# Power.net
KiCad netlist of a schematic drawn in Altium Designer
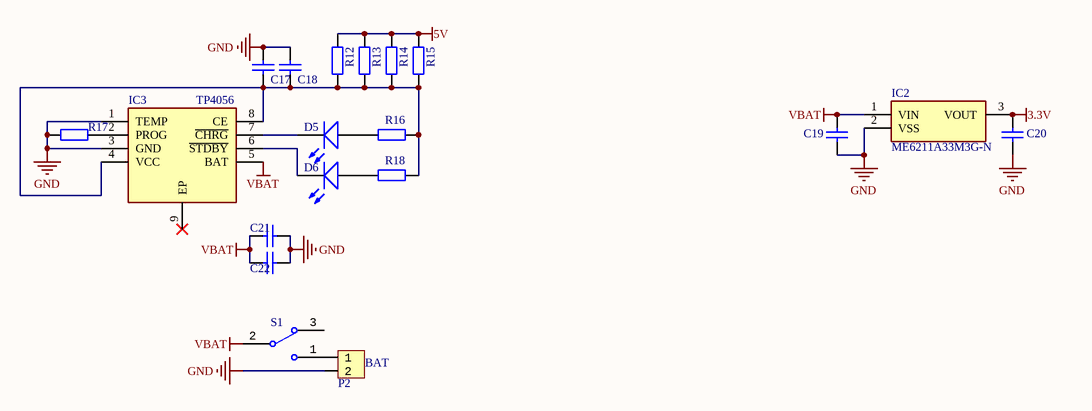
[diagram p0: Power.SchDoc]

(export (version "E")
  (design (tool "Eeschema 10.0.6"))
  (components
    (comp (ref "C17")
      (value "10nF")
      (footprint "CAP-0603")
      (description "贴片电容")
      (libsource (lib "Power_Lib_Altium") (part "CAP"))
    )
    (comp (ref "C18")
      (value "100nF")
      (footprint "CAP-0603")
      (description "贴片电容")
      (libsource (lib "Power_Lib_Altium") (part "CAP"))
    )
    (comp (ref "C19")
      (value "1uF")
      (footprint "CAP-0603")
      (description "贴片电容")
      (libsource (lib "Power_Lib_Altium") (part "CAP"))
    )
    (comp (ref "C20")
      (value "1uF")
      (footprint "CAP-0603")
      (description "贴片电容")
      (libsource (lib "Power_Lib_Altium") (part "CAP"))
    )
    (comp (ref "C21")
      (value "100nF")
      (footprint "CAP-0603")
      (description "贴片电容")
      (libsource (lib "Power_Lib_Altium") (part "CAP"))
    )
    (comp (ref "C22")
      (value "10nF")
      (footprint "CAP-0603")
      (description "贴片电容")
      (libsource (lib "Power_Lib_Altium") (part "CAP"))
    )
    (comp (ref "D5")
      (value "RED")
      (footprint "LED-0603")
      (description "发光二极管")
      (libsource (lib "Power_Lib_Altium") (part "LED"))
    )
    (comp (ref "D6")
      (value "RED")
      (footprint "LED-0603")
      (description "发光二极管")
      (libsource (lib "Power_Lib_Altium") (part "LED"))
    )
    (comp (ref "IC2")
      (value "ME6211A33M3G-N")
      (footprint "SOT-23-3")
      (description "线性稳压")
      (fields (field (name "MANUFACTURER_PART_NUMBER") "SI2302DS") (field (name "RS PART NUMBER") "7983053P"))
      (libsource (lib "Power_Lib_Altium") (part "ME6211A33M3G-N"))
    )
    (comp (ref "IC3")
      (value "TP4056")
      (footprint "MSOP_E120_P0.5_10")
      (description "锂电池充电（1A 线性）")
      (fields (field (name "MANUFACTURER_PART_NUMBER") "TP4056-42-ESOP8"))
      (libsource (lib "Power_Lib_Altium") (part "TP4056"))
    )
    (comp (ref "P2")
      (value "HDR1x2_2.54")
      (footprint "HDR1X2_2.54_90")
      (description "Header")
      (libsource (lib "Power_Lib_Altium") (part "HDR1x2_2.54"))
    )
    (comp (ref "R12")
      (value "1R")
      (footprint "R-0603")
      (description "贴片电阻")
      (libsource (lib "Power_Lib_Altium") (part "RES"))
    )
    (comp (ref "R13")
      (value "1R")
      (footprint "R-0603")
      (description "贴片电阻")
      (libsource (lib "Power_Lib_Altium") (part "RES"))
    )
    (comp (ref "R14")
      (value "1R")
      (footprint "R-0603")
      (description "贴片电阻")
      (libsource (lib "Power_Lib_Altium") (part "RES"))
    )
    (comp (ref "R15")
      (value "1R")
      (footprint "R-0603")
      (description "贴片电阻")
      (libsource (lib "Power_Lib_Altium") (part "RES"))
    )
    (comp (ref "R16")
      (value "2K")
      (footprint "R-0603")
      (description "贴片电阻")
      (libsource (lib "") (part "RES_1"))
    )
    (comp (ref "R17")
      (value "1.2K")
      (footprint "R-0603")
      (description "贴片电阻")
      (libsource (lib "") (part "RES_1"))
    )
    (comp (ref "R18")
      (value "10K")
      (footprint "R-0603")
      (description "贴片电阻")
      (libsource (lib "") (part "RES_1"))
    )
    (comp (ref "S1")
      (value "Switch_SPDT")
      (footprint "SwitchSPDT_2.8X6.6_90")
      (libsource (lib "Power_Lib_Altium") (part "Switch_SPDT"))
    )
  )
  (nets
    (net (code "1") (name "3.3V") (class "Default")
      (node (ref "C20") (pin "2") (pinfunction "2_2") (pintype "passive"))
      (node (ref "IC2") (pin "3") (pinfunction "VOUT_3") (pintype "passive"))
    )
    (net (code "2") (name "5V") (class "Default")
      (node (ref "R12") (pin "2") (pinfunction "2_2") (pintype "passive"))
      (node (ref "R13") (pin "2") (pinfunction "2_2") (pintype "passive"))
      (node (ref "R14") (pin "2") (pinfunction "2_2") (pintype "passive"))
      (node (ref "R15") (pin "2") (pinfunction "2_2") (pintype "passive"))
    )
    (net (code "3") (name "GND") (class "Default")
      (node (ref "C17") (pin "2") (pinfunction "2_2") (pintype "passive"))
      (node (ref "C18") (pin "2") (pinfunction "2_2") (pintype "passive"))
      (node (ref "C19") (pin "1") (pinfunction "1_1") (pintype "passive"))
      (node (ref "C20") (pin "1") (pinfunction "1_1") (pintype "passive"))
      (node (ref "C21") (pin "1") (pinfunction "1_1") (pintype "passive"))
      (node (ref "C22") (pin "1") (pinfunction "1_1") (pintype "passive"))
      (node (ref "IC2") (pin "2") (pinfunction "VSS_2") (pintype "passive"))
      (node (ref "IC3") (pin "1") (pinfunction "TEMP_1") (pintype "passive"))
      (node (ref "IC3") (pin "3") (pinfunction "GND_3") (pintype "passive"))
      (node (ref "P2") (pin "2") (pinfunction "2_2") (pintype "passive"))
      (node (ref "R17") (pin "1") (pinfunction "1_1") (pintype "passive"))
    )
    (net (code "4") (name "Net-(D5-PadA)") (class "Default")
      (node (ref "D5") (pin "A") (pinfunction "A_A") (pintype "passive"))
      (node (ref "R16") (pin "1") (pinfunction "1_1") (pintype "passive"))
    )
    (net (code "5") (name "Net-(D6-PadA)") (class "Default")
      (node (ref "D6") (pin "A") (pinfunction "A_A") (pintype "passive"))
      (node (ref "R18") (pin "1") (pinfunction "1_1") (pintype "passive"))
    )
    (net (code "6") (name "Net-(IC3-CE)") (class "Default")
      (node (ref "C17") (pin "1") (pinfunction "1_1") (pintype "passive"))
      (node (ref "C18") (pin "1") (pinfunction "1_1") (pintype "passive"))
      (node (ref "IC3") (pin "4") (pinfunction "VCC_4") (pintype "passive"))
      (node (ref "IC3") (pin "8") (pinfunction "CE_8") (pintype "passive"))
      (node (ref "R12") (pin "1") (pinfunction "1_1") (pintype "passive"))
      (node (ref "R13") (pin "1") (pinfunction "1_1") (pintype "passive"))
      (node (ref "R14") (pin "1") (pinfunction "1_1") (pintype "passive"))
      (node (ref "R15") (pin "1") (pinfunction "1_1") (pintype "passive"))
      (node (ref "R16") (pin "2") (pinfunction "2_2") (pintype "passive"))
      (node (ref "R18") (pin "2") (pinfunction "2_2") (pintype "passive"))
    )
    (net (code "7") (name "Net-(IC3-PROG)") (class "Default")
      (node (ref "IC3") (pin "2") (pinfunction "PROG_2") (pintype "passive"))
      (node (ref "R17") (pin "2") (pinfunction "2_2") (pintype "passive"))
    )
    (net (code "8") (name "Net-(IC3-~{CHRG})") (class "Default")
      (node (ref "D5") (pin "K") (pinfunction "K_K") (pintype "passive"))
      (node (ref "IC3") (pin "7") (pinfunction "~{CHRG}_7") (pintype "passive"))
    )
    (net (code "9") (name "Net-(IC3-~{STDBY})") (class "Default")
      (node (ref "D6") (pin "K") (pinfunction "K_K") (pintype "passive"))
      (node (ref "IC3") (pin "6") (pinfunction "~{STDBY}_6") (pintype "passive"))
    )
    (net (code "10") (name "Net-(P2-Pad1)") (class "Default")
      (node (ref "P2") (pin "1") (pinfunction "1_1") (pintype "passive"))
      (node (ref "S1") (pin "1") (pinfunction "1_1") (pintype "passive"))
    )
    (net (code "11") (name "VBAT") (class "Default")
      (node (ref "C19") (pin "2") (pinfunction "2_2") (pintype "passive"))
      (node (ref "C21") (pin "2") (pinfunction "2_2") (pintype "passive"))
      (node (ref "C22") (pin "2") (pinfunction "2_2") (pintype "passive"))
      (node (ref "IC2") (pin "1") (pinfunction "VIN_1") (pintype "passive"))
      (node (ref "IC3") (pin "5") (pinfunction "BAT_5") (pintype "passive"))
      (node (ref "S1") (pin "2") (pinfunction "2_2") (pintype "passive"))
    )
    (net (code "12") (name "unconnected-(IC3-EP-Pad9)") (class "Default")
      (node (ref "IC3") (pin "9") (pinfunction "EP_9") (pintype "passive+no_connect"))
    )
    (net (code "13") (name "unconnected-(S1-Pad3)") (class "Default")
      (node (ref "S1") (pin "3") (pinfunction "3_3") (pintype "passive"))
    )
  )
)
